# PetWaterDispenser.net
KiCad netlist of a schematic drawn in Altium Designer
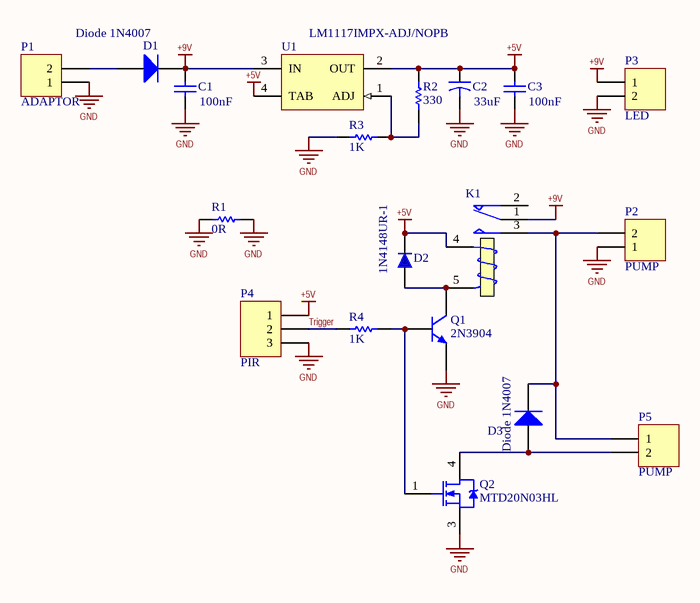
[diagram p0: PetWaterDispenser.SchDoc]

(export (version "E")
  (design (tool "Eeschema 10.0.6"))
  (components
    (comp (ref "C1")
      (value "100nF")
      (footprint "CAP_MLCC_RAD_0.1")
      (description "Capacitor")
      (fields (field (name "Comment") "Cap") (field (name "PUBLISHER") "Altium Limited"))
      (libsource (lib "Miscellaneous Devices") (part "Cap"))
    )
    (comp (ref "C2")
      (value "33uF")
      (footprint "Cap electrolitic radial 6x7-2.5")
      (description "Capacitor")
      (fields (field (name "Comment") "Cap2") (field (name "PUBLISHER") "Altium Limited"))
      (libsource (lib "Miscellaneous Devices") (part "Cap2"))
    )
    (comp (ref "C3")
      (value "100nF")
      (footprint "CAP_MLCC_RAD_0.1")
      (description "Capacitor")
      (fields (field (name "Comment") "Cap") (field (name "PUBLISHER") "Altium Limited"))
      (libsource (lib "Miscellaneous Devices") (part "Cap"))
    )
    (comp (ref "D1")
      (value "Diode 1N4007")
      (footprint "DO-204AL")
      (description "1 Amp General Purpose Rectifier")
      (fields (field (name "PUBLISHER") "Altium Limited"))
      (libsource (lib "Miscellaneous Devices") (part "Diode 1N4007"))
    )
    (comp (ref "D2")
      (value "1N4148UR-1")
      (footprint "DO 35")
      (description "DIODE GEN PURP 75V 200MA DO213AA")
      (fields (field (name "PUBLISHER") "Abbas Basereh"))
      (libsource (lib "Mofidi3D") (part "1N4148UR-1"))
    )
    (comp (ref "D3")
      (value "Diode 1N4007")
      (footprint "DO-204AL")
      (description "1 Amp General Purpose Rectifier")
      (fields (field (name "PUBLISHER") "Altium Limited"))
      (libsource (lib "Miscellaneous Devices") (part "Diode 1N4007"))
    )
    (comp (ref "K1")
      (value "~")
      (footprint "Relay 18.85x15.35x15.70")
      (description "Single-Pole Dual-Throw Relay")
      (fields (field (name "DESIGNER") "Abbas Basereh"))
      (libsource (lib "Mofidi3D") (part "Relay_SPDT"))
    )
    (comp (ref "P1")
      (value "ADAPTOR")
      (footprint "KF301 2PIN")
      (description "Header, 2-Pin")
      (fields (field (name "PUBLISHER") "Altium Limited"))
      (libsource (lib "") (part "Header 2_2"))
    )
    (comp (ref "P2")
      (value "PUMP")
      (footprint "KF301 2PIN")
      (description "Header, 2-Pin")
      (fields (field (name "PUBLISHER") "Altium Limited"))
      (libsource (lib "") (part "Header 2_1"))
    )
    (comp (ref "P3")
      (value "LED")
      (footprint "KF301 2PIN")
      (description "Header, 2-Pin")
      (fields (field (name "PUBLISHER") "Altium Limited"))
      (libsource (lib "Miscellaneous Connectors") (part "Header 2"))
    )
    (comp (ref "P4")
      (value "PIR")
      (footprint "HDR_1x3")
      (description "Header, 3-Pin")
      (fields (field (name "PUBLISHER") "Altium Limited"))
      (libsource (lib "Miscellaneous Connectors") (part "Header 3"))
    )
    (comp (ref "P5")
      (value "PUMP")
      (footprint "KF301 2PIN")
      (description "Header, 2-Pin")
      (fields (field (name "PUBLISHER") "Altium Limited"))
      (libsource (lib "Miscellaneous Connectors") (part "Header 2"))
    )
    (comp (ref "Q1")
      (value "2N3904")
      (footprint "TO-92A")
      (description "NPN General Purpose Amplifier")
      (fields (field (name "PUBLISHER") "Altium Limited"))
      (libsource (lib "Miscellaneous Devices") (part "2N3904"))
    )
    (comp (ref "Q2")
      (value "MTD20N03HL")
      (footprint "TO252-3M")
      (description "HEXFET Power MOSFET")
      (fields (field (name "PUBLISHER") "Altium Limited"))
      (libsource (lib "IR Discrete MOSFET - Power") (part "IRLR024N"))
    )
    (comp (ref "R1")
      (value "0R")
      (footprint "Axial 0_25 W, 0_4 IN LEAD PITCH")
      (description "Resistor")
      (fields (field (name "PUBLISHER") "Altium Limited"))
      (libsource (lib "Miscellaneous Devices") (part "Res1"))
    )
    (comp (ref "R2")
      (value "330")
      (footprint "RES0805")
      (description "Resistor")
      (fields (field (name "PUBLISHER") "Altium Limited"))
      (libsource (lib "Miscellaneous Devices") (part "Res1"))
    )
    (comp (ref "R3")
      (value "1K")
      (footprint "RES0805")
      (description "Resistor")
      (fields (field (name "PUBLISHER") "Altium Limited"))
      (libsource (lib "Miscellaneous Devices") (part "Res1"))
    )
    (comp (ref "R4")
      (value "1K")
      (footprint "Axial 0_25 W, 0_4 IN LEAD PITCH")
      (description "Resistor")
      (fields (field (name "PUBLISHER") "Altium Limited"))
      (libsource (lib "Miscellaneous Devices") (part "Res1"))
    )
    (comp (ref "U1")
      (value "LM1117IMPX-ADJ/NOPB")
      (footprint "SOT223_4")
      (description "800mA Low-Dropout Linear Regulator, 4-pin SOT-223, Pb-Free")
      (fields
        (field (name "MANUFACTURER") "National Semiconductor")
        (field (name "PUBLISHER") "Altium Limited")
      )
      (libsource (lib "NSC LDO") (part "LM1117IMPX-ADJ/NOPB"))
    )
  )
  (nets
    (net (code "1") (name "+5V") (class "Default")
      (node (ref "C2") (pin "1") (pinfunction "1_1") (pintype "passive"))
      (node (ref "C3") (pin "2") (pinfunction "2_2") (pintype "passive"))
      (node (ref "D2") (pin "2") (pintype "passive"))
      (node (ref "K1") (pin "4") (pinfunction "T1_4") (pintype "passive"))
      (node (ref "P4") (pin "1") (pinfunction "1_1") (pintype "passive"))
      (node (ref "R2") (pin "2") (pinfunction "2_2") (pintype "passive"))
      (node (ref "U1") (pin "2") (pinfunction "OUT_2") (pintype "power_in"))
      (node (ref "U1") (pin "4") (pinfunction "TAB_4") (pintype "power_in"))
    )
    (net (code "2") (name "+9V") (class "Default")
      (node (ref "C1") (pin "2") (pinfunction "2_2") (pintype "passive"))
      (node (ref "D1") (pin "2") (pinfunction "K_2") (pintype "passive"))
      (node (ref "K1") (pin "1") (pinfunction "COM_1") (pintype "passive"))
      (node (ref "P3") (pin "1") (pinfunction "1_1") (pintype "passive"))
      (node (ref "U1") (pin "3") (pinfunction "IN_3") (pintype "power_in"))
    )
    (net (code "3") (name "/Trigger") (class "Default")
      (node (ref "P4") (pin "2") (pinfunction "2_2") (pintype "passive"))
      (node (ref "R4") (pin "1") (pinfunction "1_1") (pintype "passive"))
    )
    (net (code "4") (name "GND") (class "Default")
      (node (ref "C1") (pin "1") (pinfunction "1_1") (pintype "passive"))
      (node (ref "C2") (pin "2") (pinfunction "2_2") (pintype "passive"))
      (node (ref "C3") (pin "1") (pinfunction "1_1") (pintype "passive"))
      (node (ref "P1") (pin "1") (pinfunction "1_1") (pintype "passive"))
      (node (ref "P2") (pin "1") (pinfunction "1_1") (pintype "passive"))
      (node (ref "P3") (pin "2") (pinfunction "2_2") (pintype "passive"))
      (node (ref "P4") (pin "3") (pinfunction "3_3") (pintype "passive"))
      (node (ref "Q1") (pin "1") (pinfunction "E_1") (pintype "passive"))
      (node (ref "Q2") (pin "3") (pinfunction "S_3") (pintype "passive"))
      (node (ref "R1") (pin "1") (pinfunction "1_1") (pintype "passive"))
      (node (ref "R1") (pin "2") (pinfunction "2_2") (pintype "passive"))
      (node (ref "R3") (pin "1") (pinfunction "1_1") (pintype "passive"))
    )
    (net (code "5") (name "Net-(D1-A)") (class "Default")
      (node (ref "D1") (pin "1") (pinfunction "A_1") (pintype "passive"))
      (node (ref "P1") (pin "2") (pinfunction "2_2") (pintype "passive"))
    )
    (net (code "6") (name "Net-(D3-A)") (class "Default")
      (node (ref "D3") (pin "1") (pinfunction "A_1") (pintype "passive"))
      (node (ref "P5") (pin "2") (pinfunction "2_2") (pintype "passive"))
      (node (ref "Q2") (pin "4") (pinfunction "D_4") (pintype "passive"))
    )
    (net (code "7") (name "Net-(D3-K)") (class "Default")
      (node (ref "D3") (pin "2") (pinfunction "K_2") (pintype "passive"))
      (node (ref "K1") (pin "3") (pinfunction "NO_3") (pintype "passive"))
      (node (ref "P2") (pin "2") (pinfunction "2_2") (pintype "passive"))
      (node (ref "P5") (pin "1") (pinfunction "1_1") (pintype "passive"))
    )
    (net (code "8") (name "Net-(K1-T2)") (class "Default")
      (node (ref "D2") (pin "1") (pintype "passive"))
      (node (ref "K1") (pin "5") (pinfunction "T2_5") (pintype "passive"))
      (node (ref "Q1") (pin "3") (pinfunction "C_3") (pintype "passive"))
    )
    (net (code "9") (name "Net-(Q1-B)") (class "Default")
      (node (ref "Q1") (pin "2") (pinfunction "B_2") (pintype "passive"))
      (node (ref "Q2") (pin "1") (pinfunction "G_1") (pintype "passive"))
      (node (ref "R4") (pin "2") (pinfunction "2_2") (pintype "passive"))
    )
    (net (code "10") (name "Net-(U1-ADJ)") (class "Default")
      (node (ref "R2") (pin "1") (pinfunction "1_1") (pintype "passive"))
      (node (ref "R3") (pin "2") (pinfunction "2_2") (pintype "passive"))
      (node (ref "U1") (pin "1") (pinfunction "ADJ_1") (pintype "input"))
    )
    (net (code "11") (name "unconnected-(K1-NC-Pad2)") (class "Default")
      (node (ref "K1") (pin "2") (pinfunction "NC_2") (pintype "passive"))
    )
  )
)
